# shuntmonitor.net
KiCad netlist of a schematic drawn in EAGLE
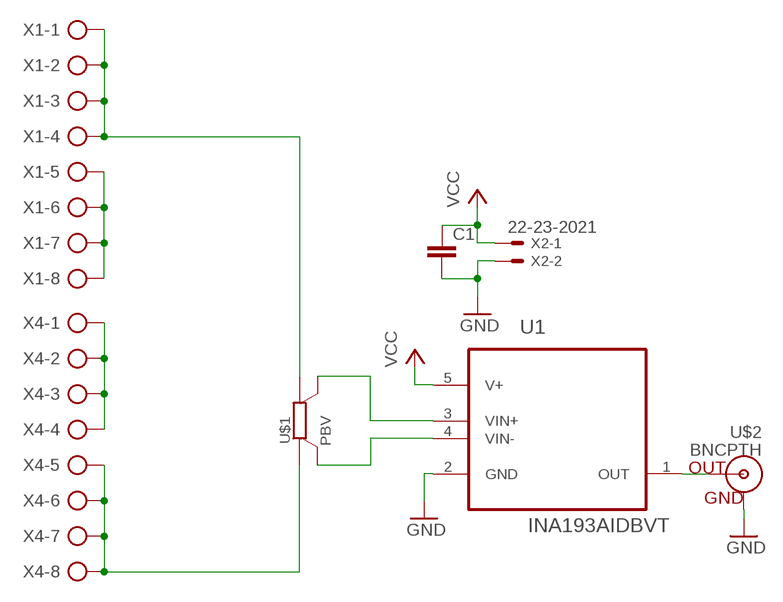
[diagram p0: schematic, sheet 1]

(export (version "E")
  (design (tool "Eeschema 10.0.6"))
  (components
    (comp (ref "C1")
      (value "C-EUC0805")
      (footprint "eagle-import:C0805")
      (libsource (lib "eagle-import") (part "C-EUC0805"))
    )
    (comp (ref "U$1")
      (value "PBV")
      (footprint "eagle-import:PBV")
      (libsource (lib "eagle-import") (part "PBV"))
    )
    (comp (ref "U$2")
      (value "BNCPTH")
      (footprint "eagle-import:BNC")
      (libsource (lib "eagle-import") (part "BNCPTH"))
    )
    (comp (ref "U1")
      (value "INA193AIDBVT")
      (footprint "eagle-import:SOT95P280X145-5N")
      (libsource (lib "eagle-import") (part "INA193AIDBVT"))
    )
    (comp (ref "X1")
      (value "AK500/8")
      (footprint "eagle-import:AK500_8")
      (libsource (lib "eagle-import") (part "AK500/8"))
    )
    (comp (ref "X2")
      (value "22-23-2021")
      (footprint "eagle-import:22-23-2021")
      (fields (field (name "MF") "MOLEX"))
      (libsource (lib "eagle-import") (part "22-23-2021"))
    )
    (comp (ref "X4")
      (value "AK500/8")
      (footprint "eagle-import:AK500_8")
      (libsource (lib "eagle-import") (part "AK500/8"))
    )
  )
  (nets
    (net (code "1") (name "GND") (class "Default")
      (node (ref "C1") (pin "2") (pinfunction "2_2") (pintype "passive"))
      (node (ref "U$2") (pin "GND") (pinfunction "GND_GND") (pintype "bidirectional"))
      (node (ref "U1") (pin "2") (pinfunction "GND_2") (pintype "passive"))
      (node (ref "X2") (pin "2") (pinfunction "S_2") (pintype "passive"))
    )
    (net (code "2") (name "Net-(U$1-A)") (class "Default")
      (node (ref "U$1") (pin "I1") (pinfunction "A_I1") (pintype "passive"))
      (node (ref "X1") (pin "1") (pinfunction "KL_1") (pintype "passive"))
      (node (ref "X1") (pin "2") (pinfunction "KL_2") (pintype "passive"))
      (node (ref "X1") (pin "3") (pinfunction "KL_3") (pintype "passive"))
      (node (ref "X1") (pin "4") (pinfunction "KL_4") (pintype "passive"))
    )
    (net (code "3") (name "Net-(U$1-B)") (class "Default")
      (node (ref "U$1") (pin "I2") (pinfunction "B_I2") (pintype "passive"))
      (node (ref "X4") (pin "5") (pinfunction "KL_5") (pintype "passive"))
      (node (ref "X4") (pin "6") (pinfunction "KL_6") (pintype "passive"))
      (node (ref "X4") (pin "7") (pinfunction "KL_7") (pintype "passive"))
      (node (ref "X4") (pin "8") (pinfunction "KL_8") (pintype "passive"))
    )
    (net (code "4") (name "Net-(U$1-SA)") (class "Default")
      (node (ref "U$1") (pin "U1") (pinfunction "SA_U1") (pintype "passive"))
      (node (ref "U1") (pin "3") (pinfunction "VIN+_3") (pintype "input"))
    )
    (net (code "5") (name "Net-(U$1-SB)") (class "Default")
      (node (ref "U$1") (pin "U2") (pinfunction "SB_U2") (pintype "passive"))
      (node (ref "U1") (pin "4") (pinfunction "VIN-_4") (pintype "input"))
    )
    (net (code "6") (name "Net-(U$2-OUT)") (class "Default")
      (node (ref "U$2") (pin "S") (pinfunction "OUT_S") (pintype "bidirectional"))
      (node (ref "U1") (pin "1") (pinfunction "OUT_1") (pintype "output"))
    )
    (net (code "7") (name "Net-(X1E-KL)") (class "Default")
      (node (ref "X1") (pin "5") (pinfunction "KL_5") (pintype "passive"))
      (node (ref "X1") (pin "6") (pinfunction "KL_6") (pintype "passive"))
      (node (ref "X1") (pin "7") (pinfunction "KL_7") (pintype "passive"))
      (node (ref "X1") (pin "8") (pinfunction "KL_8") (pintype "passive"))
    )
    (net (code "8") (name "Net-(X4A-KL)") (class "Default")
      (node (ref "X4") (pin "1") (pinfunction "KL_1") (pintype "passive"))
      (node (ref "X4") (pin "2") (pinfunction "KL_2") (pintype "passive"))
      (node (ref "X4") (pin "3") (pinfunction "KL_3") (pintype "passive"))
      (node (ref "X4") (pin "4") (pinfunction "KL_4") (pintype "passive"))
    )
    (net (code "9") (name "VCC") (class "Default")
      (node (ref "C1") (pin "1") (pinfunction "1_1") (pintype "passive"))
      (node (ref "U1") (pin "5") (pinfunction "V+_5") (pintype "power_in"))
      (node (ref "X2") (pin "1") (pinfunction "S_1") (pintype "passive"))
    )
  )
)
